# BUCK_BOOST_pre_PMIC.net
KiCad netlist of a schematic drawn in Altium Designer
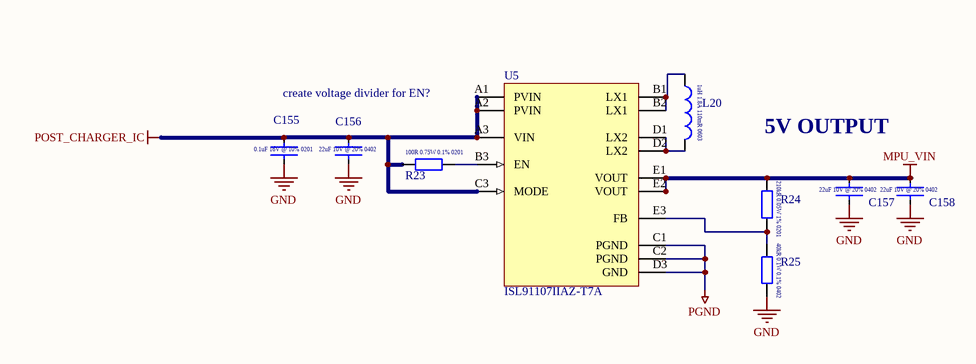
[diagram p0: BUCK BOOST pre PMIC.SchDoc]

(export (version "E")
  (design (tool "Eeschema 10.0.6"))
  (components
    (comp (ref "C155")
      (value "0.1uF")
      (footprint "CAPC0603X03L")
      (libsource (lib "Capacitors") (part "GRM033R61E104KE14J"))
    )
    (comp (ref "C156")
      (value "GRM158R61A226ME15D")
      (footprint "CAPC1005X06L")
      (description "22uH 0402")
      (libsource (lib "Capacitors") (part "GRM158R61A226ME15D"))
    )
    (comp (ref "C157")
      (value "GRM158R61A226ME15D")
      (footprint "CAPC1005X06L")
      (description "22uH 0402")
      (libsource (lib "Capacitors") (part "GRM158R61A226ME15D"))
    )
    (comp (ref "C158")
      (value "GRM158R61A226ME15D")
      (footprint "CAPC1005X06L")
      (description "22uH 0402")
      (libsource (lib "Capacitors") (part "GRM158R61A226ME15D"))
    )
    (comp (ref "L20")
      (value "IHHP0603ZHER1R0M01")
      (footprint "INDC1608LPX08L")
      (description "1 µH Shielded Inductor 1.8 A 110mOhm Max 0603 (1608 Metric)")
      (libsource (lib "Inductors") (part "IHHP0603ZHER1R0M01"))
    )
    (comp (ref "R23")
      (value "TNPW0201100RBEED")
      (footprint "RESC0603X03L")
      (libsource (lib "Resistors") (part "TNPW0201100RBEED"))
    )
    (comp (ref "R24")
      (value "ERJ-1GNF2103C")
      (footprint "RESC0603X03L")
      (description "210 kOhms ±1% 0.05W, 1/20W Chip Resistor 0201 (0603 Metric) Thick Film")
      (libsource (lib "Resistors") (part "ERJ-1GNF2103C"))
    )
    (comp (ref "R25")
      (value "RNCF0402BTE40K0")
      (footprint "RESC1005X04L")
      (description "40 kOhms ±0.1% 0.1W, 1/10W Chip Resistor 0402 (1005 Metric) Automotive AEC-Q200 Thin Film")
      (libsource (lib "Resistors") (part "RNCF0402BTE40K0"))
    )
    (comp (ref "U5")
      (value "ISL91107IIAZ-T7A")
      (footprint "W3x5_15_MFG")
      (description "ISL9110 Series 5.5 V 2.5 MHz High Efficiency Buck-Boost Regulator - WLCSP-15")
      (libsource (lib "Altium Content Vault") (part "4f4506b3ab510a19f14b30750551a47"))
    )
  )
  (nets
    (net (code "1") (name "GND") (class "Default")
      (node (ref "C155") (pin "1") (pinfunction "1_1") (pintype "passive"))
      (node (ref "C156") (pin "1") (pinfunction "1_1") (pintype "passive"))
      (node (ref "C157") (pin "1") (pinfunction "1_1") (pintype "passive"))
      (node (ref "C158") (pin "1") (pinfunction "1_1") (pintype "passive"))
      (node (ref "R25") (pin "2") (pinfunction "2_2") (pintype "passive"))
    )
    (net (code "2") (name "MPU_VIN") (class "Default")
      (node (ref "C157") (pin "2") (pinfunction "2_2") (pintype "passive"))
      (node (ref "C158") (pin "2") (pinfunction "2_2") (pintype "passive"))
      (node (ref "R24") (pin "1") (pinfunction "1_1") (pintype "passive"))
      (node (ref "U5") (pin "E1") (pinfunction "VOUT_E1") (pintype "passive"))
      (node (ref "U5") (pin "E2") (pinfunction "VOUT_E2") (pintype "passive"))
    )
    (net (code "3") (name "Net-(L20-Pad1)") (class "Default")
      (node (ref "L20") (pin "1") (pinfunction "1_1") (pintype "passive"))
      (node (ref "U5") (pin "B1") (pinfunction "LX1_B1") (pintype "passive"))
      (node (ref "U5") (pin "B2") (pinfunction "LX1_B2") (pintype "passive"))
    )
    (net (code "4") (name "Net-(L20-Pad2)") (class "Default")
      (node (ref "L20") (pin "2") (pinfunction "2_2") (pintype "passive"))
      (node (ref "U5") (pin "D1") (pinfunction "LX2_D1") (pintype "passive"))
      (node (ref "U5") (pin "D2") (pinfunction "LX2_D2") (pintype "passive"))
    )
    (net (code "5") (name "Net-(U5-EN)") (class "Default")
      (node (ref "R23") (pin "2") (pinfunction "2_2") (pintype "passive"))
      (node (ref "U5") (pin "B3") (pinfunction "EN_B3") (pintype "input"))
    )
    (net (code "6") (name "Net-(U5-FB)") (class "Default")
      (node (ref "R24") (pin "2") (pinfunction "2_2") (pintype "passive"))
      (node (ref "R25") (pin "1") (pinfunction "1_1") (pintype "passive"))
      (node (ref "U5") (pin "E3") (pinfunction "FB_E3") (pintype "passive"))
    )
    (net (code "7") (name "PGND") (class "Default")
      (node (ref "U5") (pin "C1") (pinfunction "PGND_C1") (pintype "power_in"))
      (node (ref "U5") (pin "C2") (pinfunction "PGND_C2") (pintype "power_in"))
      (node (ref "U5") (pin "D3") (pinfunction "GND_D3") (pintype "power_in"))
    )
    (net (code "8") (name "POST_CHARGER_IC") (class "Default")
      (node (ref "C155") (pin "2") (pinfunction "2_2") (pintype "passive"))
      (node (ref "C156") (pin "2") (pinfunction "2_2") (pintype "passive"))
      (node (ref "R23") (pin "1") (pinfunction "1_1") (pintype "passive"))
      (node (ref "U5") (pin "A1") (pinfunction "PVIN_A1") (pintype "power_in"))
      (node (ref "U5") (pin "A2") (pinfunction "PVIN_A2") (pintype "power_in"))
      (node (ref "U5") (pin "A3") (pinfunction "VIN_A3") (pintype "power_in"))
      (node (ref "U5") (pin "C3") (pinfunction "MODE_C3") (pintype "input"))
    )
  )
)
